# Schematic.net
KiCad netlist of a schematic drawn in EAGLE
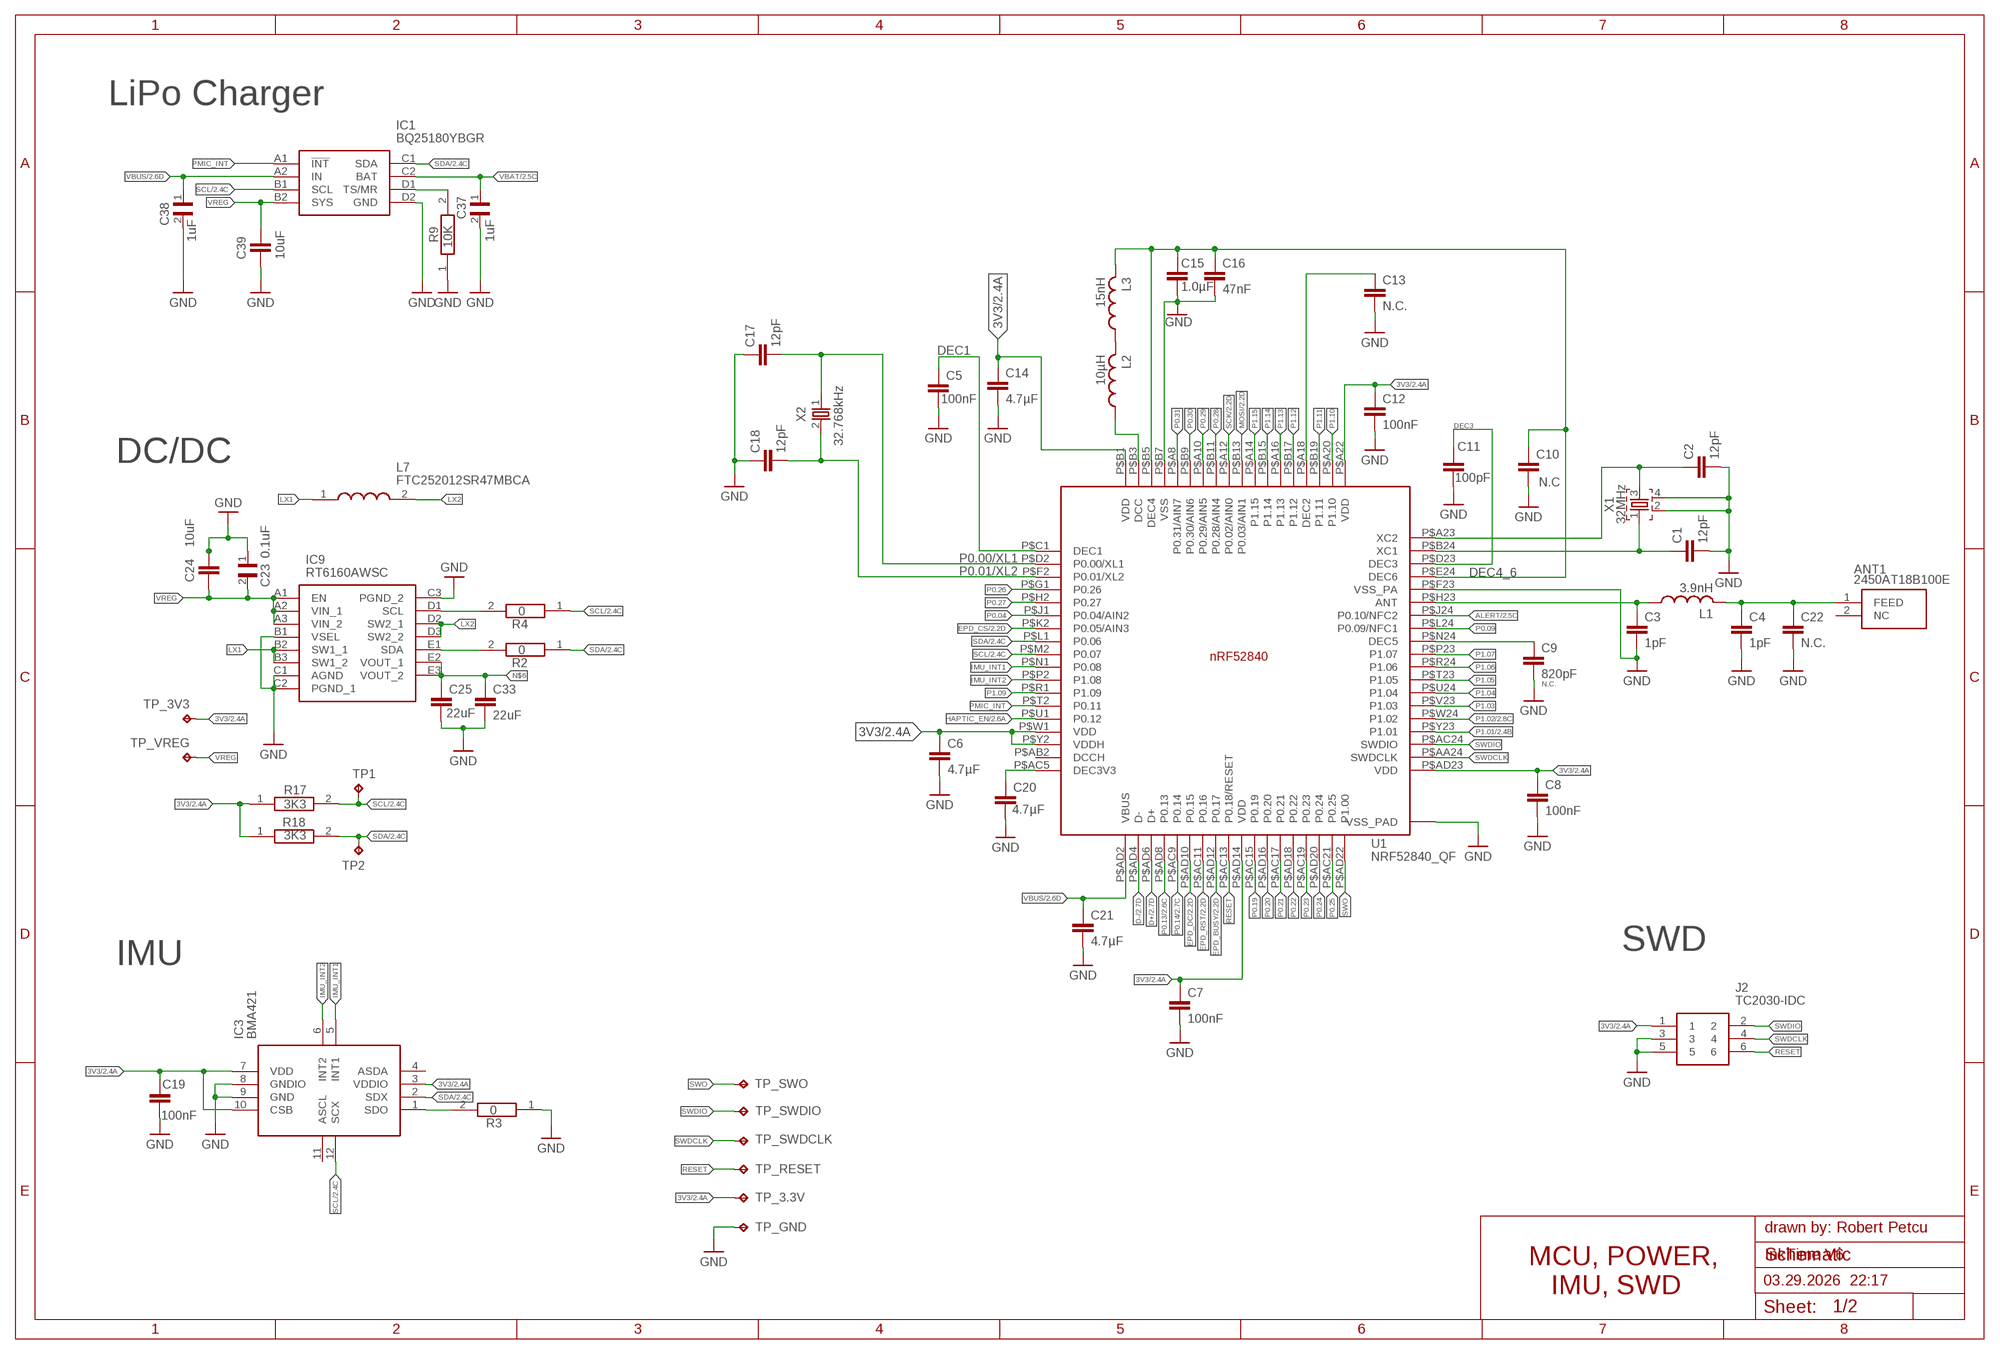
[diagram p0: schematic, sheet 1]
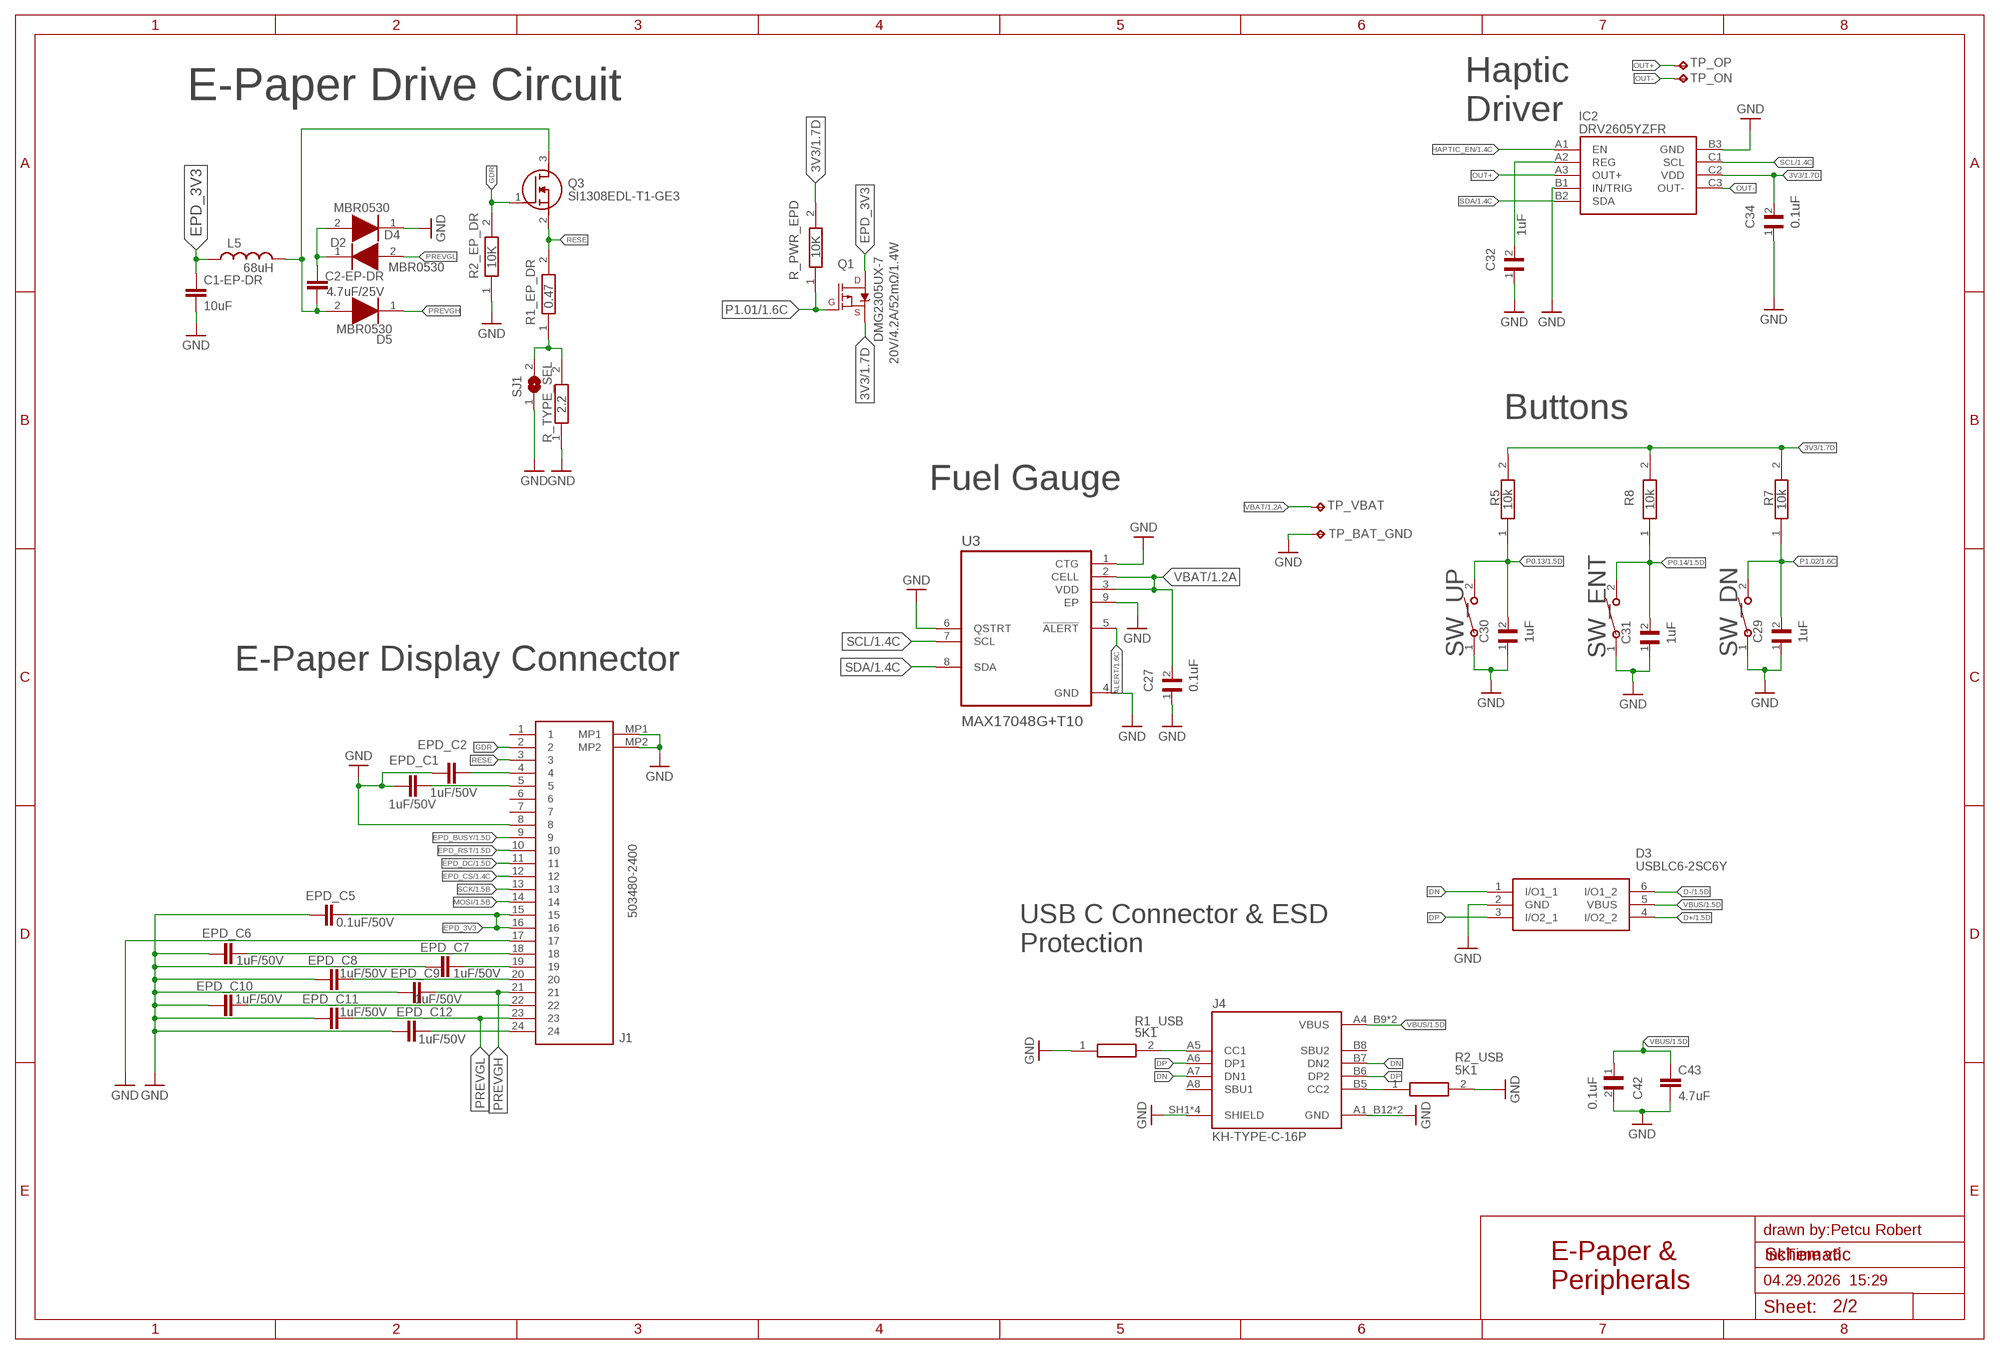
[diagram p1: schematic, sheet 2]

(export (version "E")
  (design (tool "Eeschema 10.0.6"))
  (components
    (comp (ref "ANT1")
      (value "2450AT18B100E")
      (footprint "eagle-import:2450AT18B100E_ANTC3216X140N")
      (fields (field (name "MOUSER_PART_NUMBER") "609-2450AT18B100E"))
      (libsource (lib "eagle-import") (part "2450AT18B100E_2450AT18B100E"))
    )
    (comp (ref "C1")
      (value "12pF")
      (footprint "eagle-import:NORDIC_NRF_3_RESC0201_L")
      (libsource (lib "eagle-import") (part "NORDIC_NRF_3_CAPACITOR_0201_L"))
    )
    (comp (ref "C2")
      (value "12pF")
      (footprint "eagle-import:NORDIC_NRF_3_RESC0201_L")
      (libsource (lib "eagle-import") (part "NORDIC_NRF_3_CAPACITOR_0201_L"))
    )
    (comp (ref "C3")
      (value "1pF")
      (footprint "eagle-import:NORDIC_NRF_3_RESC0201_L")
      (libsource (lib "eagle-import") (part "NORDIC_NRF_3_CAPACITOR_0201_L"))
    )
    (comp (ref "C4")
      (value "1pF")
      (footprint "eagle-import:NORDIC_NRF_3_RESC0201_L")
      (libsource (lib "eagle-import") (part "NORDIC_NRF_3_CAPACITOR_0201_L"))
    )
    (comp (ref "C5")
      (value "100nF")
      (footprint "eagle-import:NORDIC_NRF_3_RESC0201_L")
      (libsource (lib "eagle-import") (part "NORDIC_NRF_3_CAPACITOR_0201_L"))
    )
    (comp (ref "C6")
      (value "4.7µF")
      (footprint "eagle-import:PERFECT_0402_0402")
      (libsource (lib "eagle-import") (part "PERFECT_0402_CAP_0402"))
    )
    (comp (ref "C7")
      (value "100nF")
      (footprint "eagle-import:NORDIC_NRF_3_RESC0201_L")
      (libsource (lib "eagle-import") (part "NORDIC_NRF_3_CAPACITOR_0201_L"))
    )
    (comp (ref "C8")
      (value "100nF")
      (footprint "eagle-import:NORDIC_NRF_3_RESC0201_L")
      (libsource (lib "eagle-import") (part "NORDIC_NRF_3_CAPACITOR_0201_L"))
    )
    (comp (ref "C9")
      (value "820pF")
      (footprint "eagle-import:NORDIC_NRF_3_RESC0201_L")
      (libsource (lib "eagle-import") (part "NORDIC_NRF_3_CAPACITOR_0201_L"))
    )
    (comp (ref "C10")
      (value "N.C")
      (footprint "eagle-import:NORDIC_NRF_3_RESC0201_L")
      (libsource (lib "eagle-import") (part "NORDIC_NRF_3_CAPACITOR_0201_L"))
    )
    (comp (ref "C11")
      (value "100pF")
      (footprint "eagle-import:NORDIC_NRF_3_RESC0201_L")
      (libsource (lib "eagle-import") (part "NORDIC_NRF_3_CAPACITOR_0201_L"))
    )
    (comp (ref "C12")
      (value "100nF")
      (footprint "eagle-import:NORDIC_NRF_3_RESC0201_L")
      (libsource (lib "eagle-import") (part "NORDIC_NRF_3_CAPACITOR_0201_L"))
    )
    (comp (ref "C13")
      (value "N.C.")
      (footprint "eagle-import:NORDIC_NRF_3_RESC0201_L")
      (libsource (lib "eagle-import") (part "NORDIC_NRF_3_CAPACITOR_0201_L"))
    )
    (comp (ref "C14")
      (value "4.7µF")
      (footprint "eagle-import:PERFECT_0402_0402")
      (libsource (lib "eagle-import") (part "PERFECT_0402_CAP_0402"))
    )
    (comp (ref "C15")
      (value "1.0µF")
      (footprint "eagle-import:PERFECT_0402_0402")
      (libsource (lib "eagle-import") (part "PERFECT_0402_CAP_0402"))
    )
    (comp (ref "C16")
      (value "47nF")
      (footprint "eagle-import:NORDIC_NRF_3_RESC0201_L")
      (libsource (lib "eagle-import") (part "NORDIC_NRF_3_CAPACITOR_0201_L"))
    )
    (comp (ref "C17")
      (value "12pF")
      (footprint "eagle-import:NORDIC_NRF_3_RESC0201_L")
      (libsource (lib "eagle-import") (part "NORDIC_NRF_3_CAPACITOR_0201_L"))
    )
    (comp (ref "C18")
      (value "12pF")
      (footprint "eagle-import:NORDIC_NRF_3_RESC0201_L")
      (libsource (lib "eagle-import") (part "NORDIC_NRF_3_CAPACITOR_0201_L"))
    )
    (comp (ref "C19")
      (value "100nF")
      (footprint "eagle-import:NORDIC_NRF_3_RESC0201_L")
      (libsource (lib "eagle-import") (part "NORDIC_NRF_3_CAPACITOR_0201_L"))
    )
    (comp (ref "C20")
      (value "4.7µF")
      (footprint "eagle-import:PERFECT_0402_0402")
      (libsource (lib "eagle-import") (part "PERFECT_0402_CAP_0402"))
    )
    (comp (ref "C21")
      (value "4.7µF")
      (footprint "eagle-import:PERFECT_0402_0402")
      (libsource (lib "eagle-import") (part "PERFECT_0402_CAP_0402"))
    )
    (comp (ref "C22")
      (value "N.C.")
      (footprint "eagle-import:NORDIC_NRF_3_RESC0201_L")
      (libsource (lib "eagle-import") (part "NORDIC_NRF_3_CAPACITOR_0201_L"))
    )
    (comp (ref "C23")
      (value "0.1uF")
      (footprint "eagle-import:GRM011R60J152KE01L_1_0201")
      (libsource (lib "eagle-import") (part "GRM011R60J152KE01L_1_GRM011R60J152KE01L"))
    )
    (comp (ref "C24")
      (value "10uF")
      (footprint "eagle-import:PERFECT_0402_0402")
      (libsource (lib "eagle-import") (part "PERFECT_0402_CAP_0402"))
    )
    (comp (ref "C25")
      (value "22uF")
      (footprint "eagle-import:PERFECT_0402_0402")
      (libsource (lib "eagle-import") (part "PERFECT_0402_CAP_0402"))
    )
    (comp (ref "C33")
      (value "22uF")
      (footprint "eagle-import:PERFECT_0402_0402")
      (libsource (lib "eagle-import") (part "PERFECT_0402_CAP_0402"))
    )
    (comp (ref "C37")
      (value "1uF")
      (footprint "eagle-import:GRM011R60J152KE01L_1_0201")
      (libsource (lib "eagle-import") (part "GRM011R60J152KE01L_1_GRM011R60J152KE01L"))
    )
    (comp (ref "C38")
      (value "1uF")
      (footprint "eagle-import:GRM011R60J152KE01L_1_0201")
      (libsource (lib "eagle-import") (part "GRM011R60J152KE01L_1_GRM011R60J152KE01L"))
    )
    (comp (ref "C39")
      (value "10uF")
      (footprint "eagle-import:PERFECT_0402_0402")
      (libsource (lib "eagle-import") (part "PERFECT_0402_CAP_0402"))
    )
    (comp (ref "IC1")
      (value "BQ25180YBGR")
      (footprint "eagle-import:BQ25180YBGR_BGA8C40P2X4_100X155X50")
      (fields (field (name "MOUSER_PART_NUMBER") "595-BQ25180YBGR"))
      (libsource (lib "eagle-import") (part "BQ25180YBGR_BQ25180YBGR"))
    )
    (comp (ref "IC3")
      (value "BMA421")
      (footprint "eagle-import:BMA423_BMA423")
      (fields (field (name "ARROW_PART_NUMBER") "BMA423") (field (name "MOUSER_PART_NUMBER") "262-BMA423"))
      (libsource (lib "eagle-import") (part "BMA423_BMA423"))
    )
    (comp (ref "IC9")
      (value "RT6160AWSC")
      (footprint "eagle-import:RT6160AWSC_BGA15C40P3X5_140X230X60")
      (fields (field (name "MOUSER_PART_NUMBER") "835-RT6160AWSC"))
      (libsource (lib "eagle-import") (part "RT6160AWSC_RT6160AWSC"))
    )
    (comp (ref "J2")
      (value "TC2030-IDC")
      (footprint "eagle-import:TC2030-IDC_TC2030IDC")
      (libsource (lib "eagle-import") (part "TC2030-IDC_TC2030-IDC"))
    )
    (comp (ref "L1")
      (value "3.9nH")
      (footprint "eagle-import:NORDIC_NRF_2_RESC0402_L")
      (libsource (lib "eagle-import") (part "NORDIC_NRF_2_INDUCTOR_0402_L"))
    )
    (comp (ref "L2")
      (value "10µH")
      (footprint "eagle-import:NORDIC_NRF_2_RESC0402_L")
      (libsource (lib "eagle-import") (part "NORDIC_NRF_2_INDUCTOR_0402_L"))
    )
    (comp (ref "L3")
      (value "15nH")
      (footprint "eagle-import:NORDIC_NRF_2_RESC0402_L")
      (libsource (lib "eagle-import") (part "NORDIC_NRF_2_INDUCTOR_0402_L"))
    )
    (comp (ref "L7")
      (value "FTC252012SR47MBCA")
      (footprint "eagle-import:MLP2016SR47MT0S1_INDC2016X100N")
      (libsource (lib "eagle-import") (part "MLP2016SR47MT0S1_FTC252012SR47MBCA"))
    )
    (comp (ref "R2")
      (value "0")
      (footprint "eagle-import:CPF0201D7K68C1_0201")
      (libsource (lib "eagle-import") (part "CPF0201D7K68C1_CPF0201D7K68C1"))
    )
    (comp (ref "R3")
      (value "0")
      (footprint "eagle-import:CPF0201D7K68C1_0201")
      (libsource (lib "eagle-import") (part "CPF0201D7K68C1_CPF0201D7K68C1"))
    )
    (comp (ref "R4")
      (value "0")
      (footprint "eagle-import:CPF0201D7K68C1_0201")
      (libsource (lib "eagle-import") (part "CPF0201D7K68C1_CPF0201D7K68C1"))
    )
    (comp (ref "R9")
      (value "10K")
      (footprint "eagle-import:CPF0201D7K68C1_0201")
      (libsource (lib "eagle-import") (part "CPF0201D7K68C1_CPF0201D7K68C1"))
    )
    (comp (ref "R17")
      (value "3K3")
      (footprint "eagle-import:CPF0201D7K68C1_0201")
      (libsource (lib "eagle-import") (part "CPF0201D7K68C1_CPF0201D7K68C1"))
    )
    (comp (ref "R18")
      (value "3K3")
      (footprint "eagle-import:CPF0201D7K68C1_0201")
      (libsource (lib "eagle-import") (part "CPF0201D7K68C1_CPF0201D7K68C1"))
    )
    (comp (ref "TP1")
      (value "HECTOR_WATCH_1_TPTP20R")
      (footprint "eagle-import:HECTOR_WATCH_1_TP20R")
      (libsource (lib "eagle-import") (part "HECTOR_WATCH_1_TPTP20R"))
    )
    (comp (ref "TP2")
      (value "HECTOR_WATCH_1_TPTP20R")
      (footprint "eagle-import:HECTOR_WATCH_1_TP20R")
      (libsource (lib "eagle-import") (part "HECTOR_WATCH_1_TPTP20R"))
    )
    (comp (ref "TP_3.3V")
      (value "HECTOR_WATCH_1_TPTP20R")
      (footprint "eagle-import:HECTOR_WATCH_1_TP20R")
      (libsource (lib "eagle-import") (part "HECTOR_WATCH_1_TPTP20R"))
    )
    (comp (ref "TP_3V3")
      (value "HECTOR_WATCH_1_TPTP20R")
      (footprint "eagle-import:HECTOR_WATCH_1_TP20R")
      (libsource (lib "eagle-import") (part "HECTOR_WATCH_1_TPTP20R"))
    )
    (comp (ref "TP_GND")
      (value "HECTOR_WATCH_1_TPTP20R")
      (footprint "eagle-import:HECTOR_WATCH_1_TP20R")
      (libsource (lib "eagle-import") (part "HECTOR_WATCH_1_TPTP20R"))
    )
    (comp (ref "TP_RESET")
      (value "HECTOR_WATCH_1_TPTP20R")
      (footprint "eagle-import:HECTOR_WATCH_1_TP20R")
      (libsource (lib "eagle-import") (part "HECTOR_WATCH_1_TPTP20R"))
    )
    (comp (ref "TP_SWDCLK")
      (value "HECTOR_WATCH_1_TPTP20R")
      (footprint "eagle-import:HECTOR_WATCH_1_TP20R")
      (libsource (lib "eagle-import") (part "HECTOR_WATCH_1_TPTP20R"))
    )
    (comp (ref "TP_SWDIO")
      (value "HECTOR_WATCH_1_TPTP20R")
      (footprint "eagle-import:HECTOR_WATCH_1_TP20R")
      (libsource (lib "eagle-import") (part "HECTOR_WATCH_1_TPTP20R"))
    )
    (comp (ref "TP_SWO")
      (value "HECTOR_WATCH_1_TPTP20R")
      (footprint "eagle-import:HECTOR_WATCH_1_TP20R")
      (libsource (lib "eagle-import") (part "HECTOR_WATCH_1_TPTP20R"))
    )
    (comp (ref "TP_VREG")
      (value "HECTOR_WATCH_1_TPTP20R")
      (footprint "eagle-import:HECTOR_WATCH_1_TP20R")
      (libsource (lib "eagle-import") (part "HECTOR_WATCH_1_TPTP20R"))
    )
    (comp (ref "U1")
      (value "NRF52840_QF")
      (footprint "eagle-import:NORDIC_NRF_4_AQFN50P700X700X85_HS-74N")
      (libsource (lib "eagle-import") (part "NORDIC_NRF_4_NRF52840_QF"))
    )
    (comp (ref "X1")
      (value "32MHz")
      (footprint "eagle-import:NORDIC_NRF_BT-XTAL_2016_N")
      (libsource (lib "eagle-import") (part "NORDIC_NRF_XTAL_32MHZ"))
    )
    (comp (ref "X2")
      (value "32.768kHz")
      (footprint "eagle-import:NORDIC_NRF_1_XTAL_3215_N")
      (libsource (lib "eagle-import") (part "NORDIC_NRF_1_XTAL_32KHZ"))
    )
    (comp (ref "C1-EP-DR")
      (value "10uF")
      (footprint "eagle-import:PERFECT_0402_0402")
      (libsource (lib "eagle-import") (part "PERFECT_0402_CAP_0402"))
    )
    (comp (ref "C2-EP-DR")
      (value "4.7uF/25V")
      (footprint "eagle-import:PERFECT_0402_0402")
      (libsource (lib "eagle-import") (part "PERFECT_0402_CAP_0402"))
    )
    (comp (ref "C27")
      (value "0.1uF")
      (footprint "eagle-import:GRM011R60J152KE01L_1_0201")
      (libsource (lib "eagle-import") (part "GRM011R60J152KE01L_1_GRM011R60J152KE01L"))
    )
    (comp (ref "C29")
      (value "1uF")
      (footprint "eagle-import:GRM011R60J152KE01L_1_0201")
      (libsource (lib "eagle-import") (part "GRM011R60J152KE01L_1_GRM011R60J152KE01L"))
    )
    (comp (ref "C30")
      (value "1uF")
      (footprint "eagle-import:GRM011R60J152KE01L_1_0201")
      (libsource (lib "eagle-import") (part "GRM011R60J152KE01L_1_GRM011R60J152KE01L"))
    )
    (comp (ref "C31")
      (value "1uF")
      (footprint "eagle-import:GRM011R60J152KE01L_1_0201")
      (libsource (lib "eagle-import") (part "GRM011R60J152KE01L_1_GRM011R60J152KE01L"))
    )
    (comp (ref "C32")
      (value "1uF")
      (footprint "eagle-import:GRM011R60J152KE01L_1_0201")
      (libsource (lib "eagle-import") (part "GRM011R60J152KE01L_1_GRM011R60J152KE01L"))
    )
    (comp (ref "C34")
      (value "0.1uF")
      (footprint "eagle-import:GRM011R60J152KE01L_1_0201")
      (libsource (lib "eagle-import") (part "GRM011R60J152KE01L_1_GRM011R60J152KE01L"))
    )
    (comp (ref "C42")
      (value "0.1uF")
      (footprint "eagle-import:GRM011R60J152KE01L_1_0201")
      (libsource (lib "eagle-import") (part "GRM011R60J152KE01L_1_GRM011R60J152KE01L"))
    )
    (comp (ref "C43")
      (value "4.7uF")
      (footprint "eagle-import:PERFECT_0402_0402")
      (libsource (lib "eagle-import") (part "PERFECT_0402_CAP_0402"))
    )
    (comp (ref "D2")
      (value "MBR0530")
      (footprint "eagle-import:ESP32_C6_LIBRARY_5_SOD3716X135N")
      (fields (field (name "MF") "ON Semiconductor"))
      (libsource (lib "eagle-import") (part "ESP32_C6_LIBRARY_5_MBR0530"))
    )
    (comp (ref "D3")
      (value "USBLC6-2SC6Y")
      (footprint "eagle-import:ESP32_C6_LIBRARY_3_SOT95P280X145-6N")
      (fields (field (name "MF") "STMicroelectronics"))
      (libsource (lib "eagle-import") (part "ESP32_C6_LIBRARY_3_USBLC6-2SC6Y"))
    )
    (comp (ref "D4")
      (value "MBR0530")
      (footprint "eagle-import:ESP32_C6_LIBRARY_5_SOD3716X135N")
      (fields (field (name "MF") "ON Semiconductor"))
      (libsource (lib "eagle-import") (part "ESP32_C6_LIBRARY_5_MBR0530"))
    )
    (comp (ref "D5")
      (value "MBR0530")
      (footprint "eagle-import:ESP32_C6_LIBRARY_5_SOD3716X135N")
      (fields (field (name "MF") "ON Semiconductor"))
      (libsource (lib "eagle-import") (part "ESP32_C6_LIBRARY_5_MBR0530"))
    )
    (comp (ref "DMG2305UX-7")
      (value "20V/4.2A/52mΩ/1.4W")
      (footprint "eagle-import:ESP32_C6_LIBRARY_4_ESP32_C6_LIBRARY_4_ESP32_C6_LIBRARY_4_ESP32_C6_LIBRARY_4_ESP32_WROVER_SPARKFUN-DISCRETESEMI_SOT23-3")
      (libsource (lib "eagle-import") (part "ESP32_C6_LIBRARY_4_ESP32_WROVER_SPARKFUN-DISCRETESEMI_MOSFET_PCH-DMG2305UX-7"))
    )
    (comp (ref "EPD_C1")
      (value "1uF/50V")
      (footprint "eagle-import:PERFECT_0402_0402")
      (libsource (lib "eagle-import") (part "PERFECT_0402_CAP_0402"))
    )
    (comp (ref "EPD_C2")
      (value "1uF/50V")
      (footprint "eagle-import:PERFECT_0402_0402")
      (libsource (lib "eagle-import") (part "PERFECT_0402_CAP_0402"))
    )
    (comp (ref "EPD_C5")
      (value "0.1uF/50V")
      (footprint "eagle-import:NORDIC_NRF_3_RESC0201_L")
      (libsource (lib "eagle-import") (part "NORDIC_NRF_3_CAPACITOR_0201_L"))
    )
    (comp (ref "EPD_C6")
      (value "1uF/50V")
      (footprint "eagle-import:PERFECT_0402_0402")
      (libsource (lib "eagle-import") (part "PERFECT_0402_CAP_0402"))
    )
    (comp (ref "EPD_C7")
      (value "1uF/50V")
      (footprint "eagle-import:PERFECT_0402_0402")
      (libsource (lib "eagle-import") (part "PERFECT_0402_CAP_0402"))
    )
    (comp (ref "EPD_C8")
      (value "1uF/50V")
      (footprint "eagle-import:PERFECT_0402_0402")
      (libsource (lib "eagle-import") (part "PERFECT_0402_CAP_0402"))
    )
    (comp (ref "EPD_C9")
      (value "1uF/50V")
      (footprint "eagle-import:PERFECT_0402_0402")
      (libsource (lib "eagle-import") (part "PERFECT_0402_CAP_0402"))
    )
    (comp (ref "EPD_C10")
      (value "1uF/50V")
      (footprint "eagle-import:PERFECT_0402_0402")
      (libsource (lib "eagle-import") (part "PERFECT_0402_CAP_0402"))
    )
    (comp (ref "EPD_C11")
      (value "1uF/50V")
      (footprint "eagle-import:PERFECT_0402_0402")
      (libsource (lib "eagle-import") (part "PERFECT_0402_CAP_0402"))
    )
    (comp (ref "EPD_C12")
      (value "1uF/50V")
      (footprint "eagle-import:PERFECT_0402_0402")
      (libsource (lib "eagle-import") (part "PERFECT_0402_CAP_0402"))
    )
    (comp (ref "IC2")
      (value "DRV2605YZFR")
      (footprint "eagle-import:DRV2605YZFR_BGA9C50P3X3_144X144X62")
      (libsource (lib "eagle-import") (part "DRV2605YZFR_DRV2605YZFR"))
    )
    (comp (ref "J1")
      (value "503480-2400")
      (footprint "eagle-import:503480-2400_5034802400")
      (fields (field (name "MOUSER_PART_NUMBER") "538-503480-2400"))
      (libsource (lib "eagle-import") (part "503480-2400_503480-2400"))
    )
    (comp (ref "J4")
      (value "KH-TYPE-C-16P")
      (footprint "eagle-import:KH-TYPE-C-16P_KINGHELM_KH-TYPE-C-16P")
      (fields (field (name "MF") "kinghelm"))
      (libsource (lib "eagle-import") (part "KH-TYPE-C-16P_KH-TYPE-C-16P"))
    )
    (comp (ref "L5")
      (value "68uH")
      (footprint "eagle-import:NORDIC_NRF_2_RESC0402_L")
      (libsource (lib "eagle-import") (part "NORDIC_NRF_2_INDUCTOR_0402_L"))
    )
    (comp (ref "Q3")
      (value "SI1308EDL-T1-GE3")
      (footprint "eagle-import:ESP32_C6_LIBRARY_6_SOT65P210X110-3N")
      (fields (field (name "MF") "Vishay Siliconix"))
      (libsource (lib "eagle-import") (part "ESP32_C6_LIBRARY_6_SI1308EDL-T1-GE3"))
    )
    (comp (ref "R1_EP_DR")
      (value "0.47")
      (footprint "eagle-import:CPF0201D7K68C1_0201")
      (libsource (lib "eagle-import") (part "CPF0201D7K68C1_CPF0201D7K68C1"))
    )
    (comp (ref "R1_USB")
      (value "5K1")
      (footprint "eagle-import:CPF0201D7K68C1_0201")
      (libsource (lib "eagle-import") (part "CPF0201D7K68C1_CPF0201D7K68C1"))
    )
    (comp (ref "R2_EP_DR")
      (value "10K")
      (footprint "eagle-import:CPF0201D7K68C1_0201")
      (libsource (lib "eagle-import") (part "CPF0201D7K68C1_CPF0201D7K68C1"))
    )
    (comp (ref "R2_USB")
      (value "5K1")
      (footprint "eagle-import:CPF0201D7K68C1_0201")
      (libsource (lib "eagle-import") (part "CPF0201D7K68C1_CPF0201D7K68C1"))
    )
    (comp (ref "R5")
      (value "10k")
      (footprint "eagle-import:CPF0201D7K68C1_0201")
      (libsource (lib "eagle-import") (part "CPF0201D7K68C1_CPF0201D7K68C1"))
    )
    (comp (ref "R7")
      (value "10k")
      (footprint "eagle-import:CPF0201D7K68C1_0201")
      (libsource (lib "eagle-import") (part "CPF0201D7K68C1_CPF0201D7K68C1"))
    )
    (comp (ref "R8")
      (value "10k")
      (footprint "eagle-import:CPF0201D7K68C1_0201")
      (libsource (lib "eagle-import") (part "CPF0201D7K68C1_CPF0201D7K68C1"))
    )
    (comp (ref "R_PWR_EPD")
      (value "10K")
      (footprint "eagle-import:CPF0201D7K68C1_0201")
      (libsource (lib "eagle-import") (part "CPF0201D7K68C1_CPF0201D7K68C1"))
    )
    (comp (ref "R_TYPE_SEL")
      (value "2.2")
      (footprint "eagle-import:CPF0201D7K68C1_0201")
      (libsource (lib "eagle-import") (part "CPF0201D7K68C1_CPF0201D7K68C1"))
    )
    (comp (ref "SJ1")
      (value "ESP32_C6_LIBRARY_7_JUMPER_SJ")
      (footprint "eagle-import:ESP32_C6_LIBRARY_7_JUMPER_SJ")
      (libsource (lib "eagle-import") (part "ESP32_C6_LIBRARY_7_JUMPER_SJ"))
    )
    (comp (ref "SW_DN")
      (value "2025-10-22_07-23-44_LIBRARY_EVP-AKE31ASW_EVP-AKE31A_PAN")
      (footprint "eagle-import:2025-10-22_07-23-44_LIBRARY_SW_EVP-AKE31A_PAN")
      (fields
        (field (name "MANUFACTURER_PART_NUMBER") "EVP-AKE31A")
        (field (name "COPYRIGHT") "Copyright (C) 2025 Ultra Librarian. All rights reserved.")
      )
      (libsource (lib "eagle-import") (part "2025-10-22_07-23-44_LIBRARY_EVP-AKE31ASW_EVP-AKE31A_PAN"))
    )
    (comp (ref "SW_ENT")
      (value "2025-10-22_07-23-44_LIBRARY_EVP-AKE31ASW_EVP-AKE31A_PAN")
      (footprint "eagle-import:2025-10-22_07-23-44_LIBRARY_SW_EVP-AKE31A_PAN")
      (fields
        (field (name "MANUFACTURER_PART_NUMBER") "EVP-AKE31A")
        (field (name "COPYRIGHT") "Copyright (C) 2025 Ultra Librarian. All rights reserved.")
      )
      (libsource (lib "eagle-import") (part "2025-10-22_07-23-44_LIBRARY_EVP-AKE31ASW_EVP-AKE31A_PAN"))
    )
    (comp (ref "SW_UP")
      (value "2025-10-22_07-23-44_LIBRARY_EVP-AKE31ASW_EVP-AKE31A_PAN")
      (footprint "eagle-import:2025-10-22_07-23-44_LIBRARY_SW_EVP-AKE31A_PAN")
      (fields
        (field (name "MANUFACTURER_PART_NUMBER") "EVP-AKE31A")
        (field (name "COPYRIGHT") "Copyright (C) 2025 Ultra Librarian. All rights reserved.")
      )
      (libsource (lib "eagle-import") (part "2025-10-22_07-23-44_LIBRARY_EVP-AKE31ASW_EVP-AKE31A_PAN"))
    )
    (comp (ref "TP_BAT_GND")
      (value "HECTOR_WATCH_1_TPTP20R")
      (footprint "eagle-import:HECTOR_WATCH_1_TP20R")
      (libsource (lib "eagle-import") (part "HECTOR_WATCH_1_TPTP20R"))
    )
    (comp (ref "TP_ON")
      (value "HECTOR_WATCH_1_TPTP20R")
      (footprint "eagle-import:HECTOR_WATCH_1_TP20R")
      (libsource (lib "eagle-import") (part "HECTOR_WATCH_1_TPTP20R"))
    )
    (comp (ref "TP_OP")
      (value "HECTOR_WATCH_1_TPTP20R")
      (footprint "eagle-import:HECTOR_WATCH_1_TP20R")
      (libsource (lib "eagle-import") (part "HECTOR_WATCH_1_TPTP20R"))
    )
    (comp (ref "TP_VBAT")
      (value "HECTOR_WATCH_1_TPTP20R")
      (footprint "eagle-import:HECTOR_WATCH_1_TP20R")
      (libsource (lib "eagle-import") (part "HECTOR_WATCH_1_TPTP20R"))
    )
    (comp (ref "U3")
      (value "MAX17048G+T10")
      (footprint "eagle-import:ESP32_C6_LIBRARY_SON50P200X200X80-9N")
      (fields (field (name "MF") "Analog Devices"))
      (libsource (lib "eagle-import") (part "ESP32_C6_LIBRARY_MAX17048G+T10"))
    )
  )
  (nets
    (net (code "1") (name "3V3{slash}1.7D") (class "Default")
      (node (ref "C34") (pin "2") (pinfunction "2_2") (pintype "passive"))
      (node (ref "DMG2305UX-7") (pin "2") (pinfunction "S_2") (pintype "bidirectional"))
      (node (ref "IC2") (pin "C2") (pinfunction "VDD_C2") (pintype "bidirectional"))
      (node (ref "R5") (pin "2") (pinfunction "2_2") (pintype "bidirectional"))
      (node (ref "R7") (pin "2") (pinfunction "2_2") (pintype "bidirectional"))
      (node (ref "R8") (pin "2") (pinfunction "2_2") (pintype "bidirectional"))
      (node (ref "R_PWR_EPD") (pin "2") (pinfunction "2_2") (pintype "bidirectional"))
    )
    (net (code "2") (name "3V3{slash}2.4A") (class "Default")
      (node (ref "C12") (pin "1") (pinfunction "1_1") (pintype "passive"))
      (node (ref "C14") (pin "1") (pinfunction "1_1") (pintype "passive"))
      (node (ref "C19") (pin "1") (pinfunction "1_1") (pintype "passive"))
      (node (ref "C6") (pin "1") (pinfunction "1_1") (pintype "passive"))
      (node (ref "C7") (pin "1") (pinfunction "1_1") (pintype "passive"))
      (node (ref "C8") (pin "1") (pinfunction "1_1") (pintype "passive"))
      (node (ref "IC3") (pin "10") (pinfunction "CSB_10") (pintype "bidirectional"))
      (node (ref "IC3") (pin "3") (pinfunction "VDDIO_3") (pintype "bidirectional"))
      (node (ref "IC3") (pin "7") (pinfunction "VDD_7") (pintype "bidirectional"))
      (node (ref "J2") (pin "1") (pinfunction "1_1") (pintype "bidirectional"))
      (node (ref "R17") (pin "1") (pinfunction "1_1") (pintype "bidirectional"))
      (node (ref "R18") (pin "1") (pinfunction "1_1") (pintype "bidirectional"))
      (node (ref "TP_3.3V") (pin "TP") (pinfunction "TP_TP") (pintype "input"))
      (node (ref "TP_3V3") (pin "TP") (pinfunction "TP_TP") (pintype "input"))
      (node (ref "U1") (pin "P$A22") (pinfunction "VDD_P$A22") (pintype "power_in"))
      (node (ref "U1") (pin "P$AD14") (pinfunction "VDD_P$AD14") (pintype "power_in"))
      (node (ref "U1") (pin "P$AD23") (pinfunction "VDD_P$AD23") (pintype "power_in"))
      (node (ref "U1") (pin "P$B1") (pinfunction "VDD_P$B1") (pintype "power_in"))
      (node (ref "U1") (pin "P$W1") (pinfunction "VDD_P$W1") (pintype "power_in"))
      (node (ref "U1") (pin "P$Y2") (pinfunction "VDDH_P$Y2") (pintype "power_in"))
    )
    (net (code "3") (name "ALERT{slash}1.6C") (class "Default")
      (node (ref "U3") (pin "5") (pinfunction "~{ALERT}_5") (pintype "output"))
    )
    (net (code "4") (name "ALERT{slash}2.5C") (class "Default")
      (node (ref "U1") (pin "P$J24") (pinfunction "P0.10/NFC2_P$J24") (pintype "bidirectional"))
    )
    (net (code "5") (name "D+{slash}1.5D") (class "Default")
      (node (ref "D3") (pin "4") (pinfunction "I/O2_2_4") (pintype "bidirectional"))
    )
    (net (code "6") (name "D+{slash}2.7D") (class "Default")
      (node (ref "U1") (pin "P$AD6") (pinfunction "D+_P$AD6") (pintype "bidirectional"))
    )
    (net (code "7") (name "D-{slash}1.5D") (class "Default")
      (node (ref "D3") (pin "6") (pinfunction "I/O1_2_6") (pintype "bidirectional"))
    )
    (net (code "8") (name "D-{slash}2.7D") (class "Default")
      (node (ref "U1") (pin "P$AD4") (pinfunction "D-_P$AD4") (pintype "bidirectional"))
    )
    (net (code "9") (name "DEC1") (class "Default")
      (node (ref "C5") (pin "1") (pinfunction "1_1") (pintype "passive"))
      (node (ref "U1") (pin "P$C1") (pinfunction "DEC1_P$C1") (pintype "power_in"))
    )
    (net (code "10") (name "DEC3") (class "Default")
      (node (ref "C11") (pin "1") (pinfunction "1_1") (pintype "passive"))
      (node (ref "U1") (pin "P$D23") (pinfunction "DEC3_P$D23") (pintype "bidirectional"))
    )
    (net (code "11") (name "DEC4_6") (class "Default")
      (node (ref "C10") (pin "1") (pinfunction "1_1") (pintype "passive"))
      (node (ref "C15") (pin "1") (pinfunction "1_1") (pintype "passive"))
      (node (ref "C16") (pin "1") (pinfunction "1_1") (pintype "passive"))
      (node (ref "L3") (pin "2") (pinfunction "2_2") (pintype "passive"))
      (node (ref "U1") (pin "P$B5") (pinfunction "DEC4_P$B5") (pintype "power_in"))
      (node (ref "U1") (pin "P$E24") (pinfunction "DEC6_P$E24") (pintype "bidirectional"))
    )
    (net (code "12") (name "DN") (class "Default")
      (node (ref "D3") (pin "1") (pinfunction "I/O1_1_1") (pintype "bidirectional"))
      (node (ref "J4") (pin "A7") (pinfunction "DN1_A7") (pintype "bidirectional"))
      (node (ref "J4") (pin "B7") (pinfunction "DN2_B7") (pintype "bidirectional"))
    )
    (net (code "13") (name "DP") (class "Default")
      (node (ref "D3") (pin "3") (pinfunction "I/O2_1_3") (pintype "bidirectional"))
      (node (ref "J4") (pin "A6") (pinfunction "DP1_A6") (pintype "bidirectional"))
      (node (ref "J4") (pin "B6") (pinfunction "DP2_B6") (pintype "bidirectional"))
    )
    (net (code "14") (name "EPD_3V3") (class "Default")
      (node (ref "C1-EP-DR") (pin "1") (pinfunction "1_1") (pintype "passive"))
      (node (ref "DMG2305UX-7") (pin "3") (pinfunction "D_3") (pintype "bidirectional"))
      (node (ref "EPD_C5") (pin "2") (pinfunction "2_2") (pintype "passive"))
      (node (ref "J1") (pin "15") (pinfunction "15_15") (pintype "bidirectional"))
      (node (ref "J1") (pin "16") (pinfunction "16_16") (pintype "bidirectional"))
      (node (ref "L5") (pin "1") (pinfunction "1_1") (pintype "passive"))
    )
    (net (code "15") (name "EPD_BUSY{slash}1.5D") (class "Default")
      (node (ref "J1") (pin "9") (pinfunction "9_9") (pintype "bidirectional"))
    )
    (net (code "16") (name "EPD_BUSY{slash}2.2D") (class "Default")
      (node (ref "U1") (pin "P$AD12") (pinfunction "P0.17_P$AD12") (pintype "bidirectional"))
    )
    (net (code "17") (name "EPD_CS{slash}1.4C") (class "Default")
      (node (ref "J1") (pin "12") (pinfunction "12_12") (pintype "bidirectional"))
    )
    (net (code "18") (name "EPD_CS{slash}2.2D") (class "Default")
      (node (ref "U1") (pin "P$K2") (pinfunction "P0.05/AIN3_P$K2") (pintype "bidirectional"))
    )
    (net (code "19") (name "EPD_DC{slash}1.5D") (class "Default")
      (node (ref "J1") (pin "11") (pinfunction "11_11") (pintype "bidirectional"))
    )
    (net (code "20") (name "EPD_DC{slash}2.2D") (class "Default")
      (node (ref "U1") (pin "P$AD10") (pinfunction "P0.15_P$AD10") (pintype "bidirectional"))
    )
    (net (code "21") (name "EPD_RST{slash}1.5D") (class "Default")
      (node (ref "J1") (pin "10") (pinfunction "10_10") (pintype "bidirectional"))
    )
    (net (code "22") (name "EPD_RST{slash}2.2D") (class "Default")
      (node (ref "U1") (pin "P$AC11") (pinfunction "P0.16_P$AC11") (pintype "bidirectional"))
    )
    (net (code "23") (name "GDR") (class "Default")
      (node (ref "J1") (pin "2") (pinfunction "2_2") (pintype "bidirectional"))
      (node (ref "Q3") (pin "1") (pinfunction "G_1") (pintype "bidirectional"))
      (node (ref "R2_EP_DR") (pin "2") (pinfunction "2_2") (pintype "bidirectional"))
    )
    (net (code "24") (name "GND") (class "Default")
      (node (ref "C1") (pin "2") (pinfunction "2_2") (pintype "passive"))
      (node (ref "C1-EP-DR") (pin "2") (pinfunction "2_2") (pintype "passive"))
      (node (ref "C10") (pin "2") (pinfunction "2_2") (pintype "passive"))
      (node (ref "C11") (pin "2") (pinfunction "2_2") (pintype "passive"))
      (node (ref "C12") (pin "2") (pinfunction "2_2") (pintype "passive"))
      (node (ref "C13") (pin "2") (pinfunction "2_2") (pintype "passive"))
      (node (ref "C14") (pin "2") (pinfunction "2_2") (pintype "passive"))
      (node (ref "C15") (pin "2") (pinfunction "2_2") (pintype "passive"))
      (node (ref "C16") (pin "2") (pinfunction "2_2") (pintype "passive"))
      (node (ref "C17") (pin "1") (pinfunction "1_1") (pintype "passive"))
      (node (ref "C18") (pin "1") (pinfunction "1_1") (pintype "passive"))
      (node (ref "C19") (pin "2") (pinfunction "2_2") (pintype "passive"))
      (node (ref "C2") (pin "2") (pinfunction "2_2") (pintype "passive"))
      (node (ref "C20") (pin "2") (pinfunction "2_2") (pintype "passive"))
      (node (ref "C21") (pin "2") (pinfunction "2_2") (pintype "passive"))
      (node (ref "C22") (pin "2") (pinfunction "2_2") (pintype "passive"))
      (node (ref "C23") (pin "1") (pinfunction "1_1") (pintype "passive"))
      (node (ref "C24") (pin "1") (pinfunction "1_1") (pintype "passive"))
      (node (ref "C25") (pin "2") (pinfunction "2_2") (pintype "passive"))
      (node (ref "C27") (pin "1") (pinfunction "1_1") (pintype "passive"))
      (node (ref "C29") (pin "1") (pinfunction "1_1") (pintype "passive"))
      (node (ref "C3") (pin "2") (pinfunction "2_2") (pintype "passive"))
      (node (ref "C30") (pin "1") (pinfunction "1_1") (pintype "passive"))
      (node (ref "C31") (pin "1") (pinfunction "1_1") (pintype "passive"))
      (node (ref "C32") (pin "1") (pinfunction "1_1") (pintype "passive"))
      (node (ref "C33") (pin "2") (pinfunction "2_2") (pintype "passive"))
      (node (ref "C34") (pin "1") (pinfunction "1_1") (pintype "passive"))
      (node (ref "C37") (pin "2") (pinfunction "2_2") (pintype "passive"))
      (node (ref "C38") (pin "2") (pinfunction "2_2") (pintype "passive"))
      (node (ref "C39") (pin "2") (pinfunction "2_2") (pintype "passive"))
      (node (ref "C4") (pin "2") (pinfunction "2_2") (pintype "passive"))
      (node (ref "C42") (pin "2") (pinfunction "2_2") (pintype "passive"))
      (node (ref "C43") (pin "2") (pinfunction "2_2") (pintype "passive"))
      (node (ref "C5") (pin "2") (pinfunction "2_2") (pintype "passive"))
      (node (ref "C6") (pin "2") (pinfunction "2_2") (pintype "passive"))
      (node (ref "C7") (pin "2") (pinfunction "2_2") (pintype "passive"))
      (node (ref "C8") (pin "2") (pinfunction "2_2") (pintype "passive"))
      (node (ref "C9") (pin "2") (pinfunction "2_2") (pintype "passive"))
      (node (ref "D3") (pin "2") (pinfunction "GND_2") (pintype "bidirectional"))
      (node (ref "D4") (pin "1") (pinfunction "K_1") (pintype "bidirectional"))
      (node (ref "EPD_C1") (pin "1") (pinfunction "1_1") (pintype "passive"))
      (node (ref "EPD_C10") (pin "1") (pinfunction "1_1") (pintype "passive"))
      (node (ref "EPD_C11") (pin "1") (pinfunction "1_1") (pintype "passive"))
      (node (ref "EPD_C12") (pin "1") (pinfunction "1_1") (pintype "passive"))
      (node (ref "EPD_C2") (pin "1") (pinfunction "1_1") (pintype "passive"))
      (node (ref "EPD_C5") (pin "1") (pinfunction "1_1") (pintype "passive"))
      (node (ref "EPD_C6") (pin "1") (pinfunction "1_1") (pintype "passive"))
      (node (ref "EPD_C7") (pin "1") (pinfunction "1_1") (pintype "passive"))
      (node (ref "EPD_C8") (pin "1") (pinfunction "1_1") (pintype "passive"))
      (node (ref "EPD_C9") (pin "1") (pinfunction "1_1") (pintype "passive"))
      (node (ref "IC1") (pin "D2") (pinfunction "GND_D2") (pintype "bidirectional"))
      (node (ref "IC2") (pin "B1") (pinfunction "IN/TRIG_B1") (pintype "bidirectional"))
      (node (ref "IC2") (pin "B3") (pinfunction "GND_B3") (pintype "bidirectional"))
      (node (ref "IC3") (pin "8") (pinfunction "GNDIO_8") (pintype "bidirectional"))
      (node (ref "IC3") (pin "9") (pinfunction "GND_9") (pintype "bidirectional"))
      (node (ref "IC9") (pin "B1") (pinfunction "VSEL_B1") (pintype "bidirectional"))
      (node (ref "IC9") (pin "C1") (pinfunction "AGND_C1") (pintype "bidirectional"))
      (node (ref "IC9") (pin "C2") (pinfunction "PGND_1_C2") (pintype "bidirectional"))
      (node (ref "IC9") (pin "C3") (pinfunction "PGND_2_C3") (pintype "bidirectional"))
      (node (ref "J1") (pin "17") (pinfunction "17_17") (pintype "bidirectional"))
      (node (ref "J1") (pin "8") (pinfunction "8_8") (pintype "bidirectional"))
      (node (ref "J1") (pin "MP1") (pinfunction "MP1_MP1") (pintype "bidirectional"))
      (node (ref "J1") (pin "MP2") (pinfunction "MP2_MP2") (pintype "bidirectional"))
      (node (ref "J2") (pin "3") (pinfunction "3_3") (pintype "bidirectional"))
      (node (ref "J2") (pin "5") (pinfunction "5_5") (pintype "bidirectional"))
      (node (ref "J4") (pin "A12_B1") (pinfunction "GND_A12_B1") (pintype "power_in"))
      (node (ref "J4") (pin "A1_B12") (pinfunction "GND_A1_B12") (pintype "power_in"))
      (node (ref "J4") (pin "SH1") (pinfunction "SHIELD_SH1") (pintype "passive"))
      (node (ref "J4") (pin "SH2") (pinfunction "SHIELD_SH2") (pintype "passive"))
      (node (ref "J4") (pin "SH3") (pinfunction "SHIELD_SH3") (pintype "passive"))
      (node (ref "J4") (pin "SH4") (pinfunction "SHIELD_SH4") (pintype "passive"))
      (node (ref "R1_USB") (pin "1") (pinfunction "1_1") (pintype "bidirectional"))
      (node (ref "R2_EP_DR") (pin "1") (pinfunction "1_1") (pintype "bidirectional"))
      (node (ref "R2_USB") (pin "2") (pinfunction "2_2") (pintype "bidirectional"))
      (node (ref "R3") (pin "1") (pinfunction "1_1") (pintype "bidirectional"))
      (node (ref "R9") (pin "1") (pinfunction "1_1") (pintype "bidirectional"))
      (node (ref "R_TYPE_SEL") (pin "1") (pinfunction "1_1") (pintype "bidirectional"))
      (node (ref "SJ1") (pin "1") (pinfunction "1_1") (pintype "passive"))
      (node (ref "SW_DN") (pin "1") (pinfunction "1_1") (pintype "passive"))
      (node (ref "SW_ENT") (pin "1") (pinfunction "1_1") (pintype "passive"))
      (node (ref "SW_UP") (pin "1") (pinfunction "1_1") (pintype "passive"))
      (node (ref "TP_BAT_GND") (pin "TP") (pinfunction "TP_TP") (pintype "input"))
      (node (ref "TP_GND") (pin "TP") (pinfunction "TP_TP") (pintype "input"))
      (node (ref "U1") (pin "P$74") (pinfunction "VSS_PAD_P$74") (pintype "bidirectional"))
      (node (ref "U1") (pin "P$75") (pinfunction "VSS_PAD_P$75") (pintype "bidirectional"))
      (node (ref "U1") (pin "P$76") (pinfunction "VSS_PAD_P$76") (pintype "bidirectional"))
      (node (ref "U1") (pin "P$77") (pinfunction "VSS_PAD_P$77") (pintype "bidirectional"))
      (node (ref "U1") (pin "P$78") (pinfunction "VSS_PAD_P$78") (pintype "bidirectional"))
      (node (ref "U1") (pin "P$79") (pinfunction "VSS_PAD_P$79") (pintype "bidirectional"))
      (node (ref "U1") (pin "P$80") (pinfunction "VSS_PAD_P$80") (pintype "bidirectional"))
      (node (ref "U1") (pin "P$81") (pinfunction "VSS_PAD_P$81") (pintype "bidirectional"))
      (node (ref "U1") (pin "P$82") (pinfunction "VSS_PAD_P$82") (pintype "bidirectional"))
      (node (ref "U1") (pin "P$83") (pinfunction "VSS_PAD_P$83") (pintype "bidirectional"))
      (node (ref "U1") (pin "P$84") (pinfunction "VSS_PAD_P$84") (pintype "bidirectional"))
      (node (ref "U1") (pin "P$85") (pinfunction "VSS_PAD_P$85") (pintype "bidirectional"))
      (node (ref "U1") (pin "P$86") (pinfunction "VSS_PAD_P$86") (pintype "bidirectional"))
      (node (ref "U1") (pin "P$87") (pinfunction "VSS_PAD_P$87") (pintype "bidirectional"))
      (node (ref "U1") (pin "P$88") (pinfunction "VSS_PAD_P$88") (pintype "bidirectional"))
      (node (ref "U1") (pin "P$89") (pinfunction "VSS_PAD_P$89") (pintype "bidirectional"))
      (node (ref "U1") (pin "P$90") (pinfunction "VSS_PAD_P$90") (pintype "bidirectional"))
      (node (ref "U1") (pin "P$B7") (pinfunction "VSS_P$B7") (pintype "power_in"))
      (node (ref "U1") (pin "P$F23") (pinfunction "VSS_PA_P$F23") (pintype "bidirectional"))
      (node (ref "U3") (pin "1") (pinfunction "CTG_1") (pintype "power_in"))
      (node (ref "U3") (pin "4") (pinfunction "GND_4") (pintype "power_in"))
      (node (ref "U3") (pin "6") (pinfunction "QSTRT_6") (pintype "input"))
      (node (ref "U3") (pin "9") (pinfunction "EP_9") (pintype "power_in"))
      (node (ref "X1") (pin "2") (pinfunction "2_2") (pintype "passive"))
      (node (ref "X1") (pin "4") (pinfunction "4_4") (pintype "passive"))
    )
    (net (code "25") (name "HAPTIC_EN{slash}1.4C") (class "Default")
      (node (ref "IC2") (pin "A1") (pinfunction "EN_A1") (pintype "bidirectional"))
    )
    (net (code "26") (name "HAPTIC_EN{slash}2.6A") (class "Default")
      (node (ref "U1") (pin "P$U1") (pinfunction "P0.12_P$U1") (pintype "bidirectional"))
    )
    (net (code "27") (name "IMU_INT1") (class "Default")
      (node (ref "IC3") (pin "5") (pinfunction "INT1_5") (pintype "bidirectional"))
      (node (ref "U1") (pin "P$N1") (pinfunction "P0.08_P$N1") (pintype "bidirectional"))
    )
    (net (code "28") (name "IMU_INT2") (class "Default")
      (node (ref "IC3") (pin "6") (pinfunction "INT2_6") (pintype "bidirectional"))
      (node (ref "U1") (pin "P$P2") (pinfunction "P1.08_P$P2") (pintype "bidirectional"))
    )
    (net (code "29") (name "LX1") (class "Default")
      (node (ref "IC9") (pin "B2") (pinfunction "SW1_1_B2") (pintype "bidirectional"))
      (node (ref "IC9") (pin "B3") (pinfunction "SW1_2_B3") (pintype "bidirectional"))
      (node (ref "L7") (pin "1") (pinfunction "1_1") (pintype "bidirectional"))
    )
    (net (code "30") (name "LX2") (class "Default")
      (node (ref "IC9") (pin "D2") (pinfunction "SW2_1_D2") (pintype "bidirectional"))
      (node (ref "IC9") (pin "D3") (pinfunction "SW2_2_D3") (pintype "bidirectional"))
      (node (ref "L7") (pin "2") (pinfunction "2_2") (pintype "bidirectional"))
    )
    (net (code "31") (name "MOSI{slash}1.5B") (class "Default")
      (node (ref "J1") (pin "14") (pinfunction "14_14") (pintype "bidirectional"))
    )
    (net (code "32") (name "MOSI{slash}2.2D") (class "Default")
      (node (ref "U1") (pin "P$B13") (pinfunction "P0.03/AIN1_P$B13") (pintype "bidirectional"))
    )
    (net (code "33") (name "N$6") (class "Default")
      (node (ref "C25") (pin "1") (pinfunction "1_1") (pintype "passive"))
      (node (ref "C33") (pin "1") (pinfunction "1_1") (pintype "passive"))
      (node (ref "IC9") (pin "E2") (pinfunction "VOUT_1_E2") (pintype "bidirectional"))
      (node (ref "IC9") (pin "E3") (pinfunction "VOUT_2_E3") (pintype "bidirectional"))
    )
    (net (code "34") (name "Net-(ANT1-FEED)") (class "Default")
      (node (ref "ANT1") (pin "1") (pinfunction "FEED_1") (pintype "input"))
      (node (ref "C22") (pin "1") (pinfunction "1_1") (pintype "passive"))
      (node (ref "C4") (pin "1") (pinfunction "1_1") (pintype "passive"))
      (node (ref "L1") (pin "2") (pinfunction "2_2") (pintype "passive"))
    )
    (net (code "35") (name "Net-(D2-K)") (class "Default")
      (node (ref "C2-EP-DR") (pin "1") (pinfunction "1_1") (pintype "passive"))
      (node (ref "D2") (pin "1") (pinfunction "K_1") (pintype "bidirectional"))
      (node (ref "D4") (pin "2") (pinfunction "A_2") (pintype "bidirectional"))
    )
    (net (code "36") (name "Net-(D5-A)") (class "Default")
      (node (ref "C2-EP-DR") (pin "2") (pinfunction "2_2") (pintype "passive"))
      (node (ref "D5") (pin "2") (pinfunction "A_2") (pintype "bidirectional"))
      (node (ref "L5") (pin "2") (pinfunction "2_2") (pintype "passive"))
      (node (ref "Q3") (pin "3") (pinfunction "D_3") (pintype "bidirectional"))
    )
    (net (code "37") (name "Net-(EPD_C1-Pad2)") (class "Default")
      (node (ref "EPD_C1") (pin "2") (pinfunction "2_2") (pintype "passive"))
      (node (ref "J1") (pin "5") (pinfunction "5_5") (pintype "bidirectional"))
    )
    (net (code "38") (name "Net-(EPD_C2-Pad2)") (class "Default")
      (node (ref "EPD_C2") (pin "2") (pinfunction "2_2") (pintype "passive"))
      (node (ref "J1") (pin "4") (pinfunction "4_4") (pintype "bidirectional"))
    )
    (net (code "39") (name "Net-(EPD_C6-Pad2)") (class "Default")
      (node (ref "EPD_C6") (pin "2") (pinfunction "2_2") (pintype "passive"))
      (node (ref "J1") (pin "18") (pinfunction "18_18") (pintype "bidirectional"))
    )
    (net (code "40") (name "Net-(EPD_C7-Pad2)") (class "Default")
      (node (ref "EPD_C7") (pin "2") (pinfunction "2_2") (pintype "passive"))
      (node (ref "J1") (pin "19") (pinfunction "19_19") (pintype "bidirectional"))
    )
    (net (code "41") (name "Net-(EPD_C8-Pad2)") (class "Default")
      (node (ref "EPD_C8") (pin "2") (pinfunction "2_2") (pintype "passive"))
      (node (ref "J1") (pin "20") (pinfunction "20_20") (pintype "bidirectional"))
    )
    (net (code "42") (name "Net-(EPD_C10-Pad2)") (class "Default")
      (node (ref "EPD_C10") (pin "2") (pinfunction "2_2") (pintype "passive"))
      (node (ref "J1") (pin "22") (pinfunction "22_22") (pintype "bidirectional"))
    )
    (net (code "43") (name "Net-(EPD_C12-Pad2)") (class "Default")
      (node (ref "EPD_C12") (pin "2") (pinfunction "2_2") (pintype "passive"))
      (node (ref "J1") (pin "24") (pinfunction "24_24") (pintype "bidirectional"))
    )
    (net (code "44") (name "Net-(IC1-TS{slash}MR)") (class "Default")
      (node (ref "IC1") (pin "D1") (pinfunction "TS/MR_D1") (pintype "bidirectional"))
      (node (ref "R9") (pin "2") (pinfunction "2_2") (pintype "bidirectional"))
    )
    (net (code "45") (name "Net-(IC2-REG)") (class "Default")
      (node (ref "C32") (pin "2") (pinfunction "2_2") (pintype "passive"))
      (node (ref "IC2") (pin "A2") (pinfunction "REG_A2") (pintype "bidirectional"))
    )
    (net (code "46") (name "Net-(IC3-SDO)") (class "Default")
      (node (ref "IC3") (pin "1") (pinfunction "SDO_1") (pintype "bidirectional"))
      (node (ref "R3") (pin "2") (pinfunction "2_2") (pintype "bidirectional"))
    )
    (net (code "47") (name "Net-(IC9-SCL)") (class "Default")
      (node (ref "IC9") (pin "D1") (pinfunction "SCL_D1") (pintype "bidirectional"))
      (node (ref "R4") (pin "2") (pinfunction "2_2") (pintype "bidirectional"))
    )
    (net (code "48") (name "Net-(IC9-SDA)") (class "Default")
      (node (ref "IC9") (pin "E1") (pinfunction "SDA_E1") (pintype "bidirectional"))
      (node (ref "R2") (pin "2") (pinfunction "2_2") (pintype "bidirectional"))
    )
    (net (code "49") (name "Net-(J4-CC1)") (class "Default")
      (node (ref "J4") (pin "A5") (pinfunction "CC1_A5") (pintype "bidirectional"))
      (node (ref "R1_USB") (pin "2") (pinfunction "2_2") (pintype "bidirectional"))
    )
    (net (code "50") (name "Net-(J4-CC2)") (class "Default")
      (node (ref "J4") (pin "B5") (pinfunction "CC2_B5") (pintype "bidirectional"))
      (node (ref "R2_USB") (pin "1") (pinfunction "1_1") (pintype "bidirectional"))
    )
    (net (code "51") (name "Net-(L2-Pad2)") (class "Default")
      (node (ref "L2") (pin "2") (pinfunction "2_2") (pintype "passive"))
      (node (ref "L3") (pin "1") (pinfunction "1_1") (pintype "passive"))
    )
    (net (code "52") (name "Net-(R1_EP_DR-Pad1)") (class "Default")
      (node (ref "R1_EP_DR") (pin "1") (pinfunction "1_1") (pintype "bidirectional"))
      (node (ref "R_TYPE_SEL") (pin "2") (pinfunction "2_2") (pintype "bidirectional"))
      (node (ref "SJ1") (pin "2") (pinfunction "2_2") (pintype "passive"))
    )
    (net (code "53") (name "Net-(U1-ANT)") (class "Default")
      (node (ref "C3") (pin "1") (pinfunction "1_1") (pintype "passive"))
      (node (ref "L1") (pin "1") (pinfunction "1_1") (pintype "passive"))
      (node (ref "U1") (pin "P$H23") (pinfunction "ANT_P$H23") (pintype "bidirectional"))
    )
    (net (code "54") (name "Net-(U1-DCC)") (class "Default")
      (node (ref "L2") (pin "1") (pinfunction "1_1") (pintype "passive"))
      (node (ref "U1") (pin "P$B3") (pinfunction "DCC_P$B3") (pintype "output"))
    )
    (net (code "55") (name "Net-(U1-DEC2)") (class "Default")
      (node (ref "C13") (pin "1") (pinfunction "1_1") (pintype "passive"))
      (node (ref "U1") (pin "P$A18") (pinfunction "DEC2_P$A18") (pintype "bidirectional"))
    )
    (net (code "56") (name "Net-(U1-DEC3V3)") (class "Default")
      (node (ref "C20") (pin "1") (pinfunction "1_1") (pintype "passive"))
      (node (ref "U1") (pin "P$AC5") (pinfunction "DEC3V3_P$AC5") (pintype "bidirectional"))
    )
    (net (code "57") (name "Net-(U1-DEC5)") (class "Default")
      (node (ref "C9") (pin "1") (pinfunction "1_1") (pintype "passive"))
      (node (ref "U1") (pin "P$N24") (pinfunction "DEC5_P$N24") (pintype "bidirectional"))
    )
    (net (code "58") (name "Net-(U1-XC1)") (class "Default")
      (node (ref "C1") (pin "1") (pinfunction "1_1") (pintype "passive"))
      (node (ref "U1") (pin "P$B24") (pinfunction "XC1_P$B24") (pintype "input"))
      (node (ref "X1") (pin "1") (pinfunction "1_1") (pintype "passive"))
    )
    (net (code "59") (name "Net-(U1-XC2)") (class "Default")
      (node (ref "C2") (pin "1") (pinfunction "1_1") (pintype "passive"))
      (node (ref "U1") (pin "P$A23") (pinfunction "XC2_P$A23") (pintype "output"))
      (node (ref "X1") (pin "3") (pinfunction "3_3") (pintype "passive"))
    )
    (net (code "60") (name "OUT+") (class "Default")
      (node (ref "IC2") (pin "A3") (pinfunction "OUT+_A3") (pintype "bidirectional"))
      (node (ref "TP_OP") (pin "TP") (pinfunction "TP_TP") (pintype "input"))
    )
    (net (code "61") (name "OUT-") (class "Default")
      (node (ref "IC2") (pin "C3") (pinfunction "OUT-_C3") (pintype "bidirectional"))
      (node (ref "TP_ON") (pin "TP") (pinfunction "TP_TP") (pintype "input"))
    )
    (net (code "62") (name "P0.00{slash}XL1") (class "Default")
      (node (ref "C17") (pin "2") (pinfunction "2_2") (pintype "passive"))
      (node (ref "U1") (pin "P$D2") (pinfunction "P0.00/XL1_P$D2") (pintype "bidirectional"))
      (node (ref "X2") (pin "1") (pinfunction "1_1") (pintype "passive"))
    )
    (net (code "63") (name "P0.01{slash}XL2") (class "Default")
      (node (ref "C18") (pin "2") (pinfunction "2_2") (pintype "passive"))
      (node (ref "U1") (pin "P$F2") (pinfunction "P0.01/XL2_P$F2") (pintype "bidirectional"))
      (node (ref "X2") (pin "2") (pinfunction "2_2") (pintype "passive"))
    )
    (net (code "64") (name "P0.04") (class "Default")
      (node (ref "U1") (pin "P$J1") (pinfunction "P0.04/AIN2_P$J1") (pintype "bidirectional"))
    )
    (net (code "65") (name "P0.09") (class "Default")
      (node (ref "U1") (pin "P$L24") (pinfunction "P0.09/NFC1_P$L24") (pintype "bidirectional"))
    )
    (net (code "66") (name "P0.13{slash}1.5D") (class "Default")
      (node (ref "C30") (pin "2") (pinfunction "2_2") (pintype "passive"))
      (node (ref "R5") (pin "1") (pinfunction "1_1") (pintype "bidirectional"))
      (node (ref "SW_UP") (pin "2") (pinfunction "2_2") (pintype "passive"))
    )
    (net (code "67") (name "P0.13{slash}2.6C") (class "Default")
      (node (ref "U1") (pin "P$AD8") (pinfunction "P0.13_P$AD8") (pintype "bidirectional"))
    )
    (net (code "68") (name "P0.14{slash}1.5D") (class "Default")
      (node (ref "C31") (pin "2") (pinfunction "2_2") (pintype "passive"))
      (node (ref "R8") (pin "1") (pinfunction "1_1") (pintype "bidirectional"))
      (node (ref "SW_ENT") (pin "2") (pinfunction "2_2") (pintype "passive"))
    )
    (net (code "69") (name "P0.14{slash}2.7C") (class "Default")
      (node (ref "U1") (pin "P$AC9") (pinfunction "P0.14_P$AC9") (pintype "bidirectional"))
    )
    (net (code "70") (name "P0.19") (class "Default")
      (node (ref "U1") (pin "P$AC15") (pinfunction "P0.19_P$AC15") (pintype "bidirectional"))
    )
    (net (code "71") (name "P0.20") (class "Default")
      (node (ref "U1") (pin "P$AD16") (pinfunction "P0.20_P$AD16") (pintype "bidirectional"))
    )
    (net (code "72") (name "P0.21") (class "Default")
      (node (ref "U1") (pin "P$AC17") (pinfunction "P0.21_P$AC17") (pintype "bidirectional"))
    )
    (net (code "73") (name "P0.22") (class "Default")
      (node (ref "U1") (pin "P$AD18") (pinfunction "P0.22_P$AD18") (pintype "bidirectional"))
    )
    (net (code "74") (name "P0.23") (class "Default")
      (node (ref "U1") (pin "P$AC19") (pinfunction "P0.23_P$AC19") (pintype "bidirectional"))
    )
    (net (code "75") (name "P0.24") (class "Default")
      (node (ref "U1") (pin "P$AD20") (pinfunction "P0.24_P$AD20") (pintype "bidirectional"))
    )
    (net (code "76") (name "P0.25") (class "Default")
      (node (ref "U1") (pin "P$AC21") (pinfunction "P0.25_P$AC21") (pintype "bidirectional"))
    )
    (net (code "77") (name "P0.26") (class "Default")
      (node (ref "U1") (pin "P$G1") (pinfunction "P0.26_P$G1") (pintype "bidirectional"))
    )
    (net (code "78") (name "P0.27") (class "Default")
      (node (ref "U1") (pin "P$H2") (pinfunction "P0.27_P$H2") (pintype "bidirectional"))
    )
    (net (code "79") (name "P0.28") (class "Default")
      (node (ref "U1") (pin "P$B11") (pinfunction "P0.28/AIN4_P$B11") (pintype "bidirectional"))
    )
    (net (code "80") (name "P0.29") (class "Default")
      (node (ref "U1") (pin "P$A10") (pinfunction "P0.29/AIN5_P$A10") (pintype "bidirectional"))
    )
    (net (code "81") (name "P0.30") (class "Default")
      (node (ref "U1") (pin "P$B9") (pinfunction "P0.30/AIN6_P$B9") (pintype "bidirectional"))
    )
    (net (code "82") (name "P0.31") (class "Default")
      (node (ref "U1") (pin "P$A8") (pinfunction "P0.31/AIN7_P$A8") (pintype "bidirectional"))
    )
    (net (code "83") (name "P1.01{slash}1.6C") (class "Default")
      (node (ref "DMG2305UX-7") (pin "1") (pinfunction "G_1") (pintype "bidirectional"))
      (node (ref "R_PWR_EPD") (pin "1") (pinfunction "1_1") (pintype "bidirectional"))
    )
    (net (code "84") (name "P1.01{slash}2.4B") (class "Default")
      (node (ref "U1") (pin "P$Y23") (pinfunction "P1.01_P$Y23") (pintype "bidirectional"))
    )
    (net (code "85") (name "P1.02{slash}1.6C") (class "Default")
      (node (ref "C29") (pin "2") (pinfunction "2_2") (pintype "passive"))
      (node (ref "R7") (pin "1") (pinfunction "1_1") (pintype "bidirectional"))
      (node (ref "SW_DN") (pin "2") (pinfunction "2_2") (pintype "passive"))
    )
    (net (code "86") (name "P1.02{slash}2.8C") (class "Default")
      (node (ref "U1") (pin "P$W24") (pinfunction "P1.02_P$W24") (pintype "bidirectional"))
    )
    (net (code "87") (name "P1.03") (class "Default")
      (node (ref "U1") (pin "P$V23") (pinfunction "P1.03_P$V23") (pintype "bidirectional"))
    )
    (net (code "88") (name "P1.04") (class "Default")
      (node (ref "U1") (pin "P$U24") (pinfunction "P1.04_P$U24") (pintype "bidirectional"))
    )
    (net (code "89") (name "P1.05") (class "Default")
      (node (ref "U1") (pin "P$T23") (pinfunction "P1.05_P$T23") (pintype "bidirectional"))
    )
    (net (code "90") (name "P1.06") (class "Default")
      (node (ref "U1") (pin "P$R24") (pinfunction "P1.06_P$R24") (pintype "bidirectional"))
    )
    (net (code "91") (name "P1.07") (class "Default")
      (node (ref "U1") (pin "P$P23") (pinfunction "P1.07_P$P23") (pintype "bidirectional"))
    )
    (net (code "92") (name "P1.09") (class "Default")
      (node (ref "U1") (pin "P$R1") (pinfunction "P1.09_P$R1") (pintype "bidirectional"))
    )
    (net (code "93") (name "P1.10") (class "Default")
      (node (ref "U1") (pin "P$A20") (pinfunction "P1.10_P$A20") (pintype "bidirectional"))
    )
    (net (code "94") (name "P1.11") (class "Default")
      (node (ref "U1") (pin "P$B19") (pinfunction "P1.11_P$B19") (pintype "bidirectional"))
    )
    (net (code "95") (name "P1.12") (class "Default")
      (node (ref "U1") (pin "P$B17") (pinfunction "P1.12_P$B17") (pintype "bidirectional"))
    )
    (net (code "96") (name "P1.13") (class "Default")
      (node (ref "U1") (pin "P$A16") (pinfunction "P1.13_P$A16") (pintype "bidirectional"))
    )
    (net (code "97") (name "P1.14") (class "Default")
      (node (ref "U1") (pin "P$B15") (pinfunction "P1.14_P$B15") (pintype "bidirectional"))
    )
    (net (code "98") (name "P1.15") (class "Default")
      (node (ref "U1") (pin "P$A14") (pinfunction "P1.15_P$A14") (pintype "bidirectional"))
    )
    (net (code "99") (name "PMIC_INT") (class "Default")
      (node (ref "IC1") (pin "A1") (pinfunction "~{INT}_A1") (pintype "bidirectional"))
      (node (ref "U1") (pin "P$T2") (pinfunction "P0.11_P$T2") (pintype "bidirectional"))
    )
    (net (code "100") (name "PREVGH") (class "Default")
      (node (ref "D5") (pin "1") (pinfunction "K_1") (pintype "bidirectional"))
      (node (ref "EPD_C9") (pin "2") (pinfunction "2_2") (pintype "passive"))
      (node (ref "J1") (pin "21") (pinfunction "21_21") (pintype "bidirectional"))
    )
    (net (code "101") (name "PREVGL") (class "Default")
      (node (ref "D2") (pin "2") (pinfunction "A_2") (pintype "bidirectional"))
      (node (ref "EPD_C11") (pin "2") (pinfunction "2_2") (pintype "passive"))
      (node (ref "J1") (pin "23") (pinfunction "23_23") (pintype "bidirectional"))
    )
    (net (code "102") (name "RESE") (class "Default")
      (node (ref "J1") (pin "3") (pinfunction "3_3") (pintype "bidirectional"))
      (node (ref "Q3") (pin "2") (pinfunction "S_2") (pintype "bidirectional"))
      (node (ref "R1_EP_DR") (pin "2") (pinfunction "2_2") (pintype "bidirectional"))
    )
    (net (code "103") (name "RESET") (class "Default")
      (node (ref "J2") (pin "6") (pinfunction "6_6") (pintype "bidirectional"))
      (node (ref "TP_RESET") (pin "TP") (pinfunction "TP_TP") (pintype "input"))
      (node (ref "U1") (pin "P$AC13") (pinfunction "P0.18/RESET_P$AC13") (pintype "bidirectional"))
    )
    (net (code "104") (name "SCK{slash}1.5B") (class "Default")
      (node (ref "J1") (pin "13") (pinfunction "13_13") (pintype "bidirectional"))
    )
    (net (code "105") (name "SCK{slash}2.2D") (class "Default")
      (node (ref "U1") (pin "P$A12") (pinfunction "P0.02/AIN0_P$A12") (pintype "bidirectional"))
    )
    (net (code "106") (name "SCL{slash}1.4C") (class "Default")
      (node (ref "IC2") (pin "C1") (pinfunction "SCL_C1") (pintype "bidirectional"))
      (node (ref "U3") (pin "7") (pinfunction "SCL_7") (pintype "input"))
    )
    (net (code "107") (name "SCL{slash}2.4C") (class "Default")
      (node (ref "IC1") (pin "B1") (pinfunction "SCL_B1") (pintype "bidirectional"))
      (node (ref "IC3") (pin "12") (pinfunction "SCX_12") (pintype "bidirectional"))
      (node (ref "R17") (pin "2") (pinfunction "2_2") (pintype "bidirectional"))
      (node (ref "R4") (pin "1") (pinfunction "1_1") (pintype "bidirectional"))
      (node (ref "TP1") (pin "TP") (pinfunction "TP_TP") (pintype "input"))
      (node (ref "U1") (pin "P$M2") (pinfunction "P0.07_P$M2") (pintype "bidirectional"))
    )
    (net (code "108") (name "SDA{slash}1.4C") (class "Default")
      (node (ref "IC2") (pin "B2") (pinfunction "SDA_B2") (pintype "bidirectional"))
      (node (ref "U3") (pin "8") (pinfunction "SDA_8") (pintype "bidirectional"))
    )
    (net (code "109") (name "SDA{slash}2.4C") (class "Default")
      (node (ref "IC1") (pin "C1") (pinfunction "SDA_C1") (pintype "bidirectional"))
      (node (ref "IC3") (pin "2") (pinfunction "SDX_2") (pintype "bidirectional"))
      (node (ref "R18") (pin "2") (pinfunction "2_2") (pintype "bidirectional"))
      (node (ref "R2") (pin "1") (pinfunction "1_1") (pintype "bidirectional"))
      (node (ref "TP2") (pin "TP") (pinfunction "TP_TP") (pintype "input"))
      (node (ref "U1") (pin "P$L1") (pinfunction "P0.06_P$L1") (pintype "bidirectional"))
    )
    (net (code "110") (name "SWDCLK") (class "Default")
      (node (ref "J2") (pin "4") (pinfunction "4_4") (pintype "bidirectional"))
      (node (ref "TP_SWDCLK") (pin "TP") (pinfunction "TP_TP") (pintype "input"))
      (node (ref "U1") (pin "P$AA24") (pinfunction "SWDCLK_P$AA24") (pintype "input"))
    )
    (net (code "111") (name "SWDIO") (class "Default")
      (node (ref "J2") (pin "2") (pinfunction "2_2") (pintype "bidirectional"))
      (node (ref "TP_SWDIO") (pin "TP") (pinfunction "TP_TP") (pintype "input"))
      (node (ref "U1") (pin "P$AC24") (pinfunction "SWDIO_P$AC24") (pintype "bidirectional"))
    )
    (net (code "112") (name "SWO") (class "Default")
      (node (ref "TP_SWO") (pin "TP") (pinfunction "TP_TP") (pintype "input"))
      (node (ref "U1") (pin "P$AD22") (pinfunction "P1.00_P$AD22") (pintype "bidirectional"))
    )
    (net (code "113") (name "VBAT{slash}1.2A") (class "Default")
      (node (ref "C27") (pin "2") (pinfunction "2_2") (pintype "passive"))
      (node (ref "TP_VBAT") (pin "TP") (pinfunction "TP_TP") (pintype "input"))
      (node (ref "U3") (pin "2") (pinfunction "CELL_2") (pintype "power_in"))
      (node (ref "U3") (pin "3") (pinfunction "VDD_3") (pintype "power_in"))
    )
    (net (code "114") (name "VBAT{slash}2.5C") (class "Default")
      (node (ref "C37") (pin "1") (pinfunction "1_1") (pintype "passive"))
      (node (ref "IC1") (pin "C2") (pinfunction "BAT_C2") (pintype "bidirectional"))
    )
    (net (code "115") (name "VBUS{slash}1.5D") (class "Default")
      (node (ref "C42") (pin "1") (pinfunction "1_1") (pintype "passive"))
      (node (ref "C43") (pin "1") (pinfunction "1_1") (pintype "passive"))
      (node (ref "D3") (pin "5") (pinfunction "VBUS_5") (pintype "bidirectional"))
      (node (ref "J4") (pin "A4_B9") (pinfunction "VBUS_A4_B9") (pintype "power_in"))
      (node (ref "J4") (pin "A9_B4") (pinfunction "VBUS_A9_B4") (pintype "power_in"))
    )
    (net (code "116") (name "VBUS{slash}2.6D") (class "Default")
      (node (ref "C21") (pin "1") (pinfunction "1_1") (pintype "passive"))
      (node (ref "C38") (pin "1") (pinfunction "1_1") (pintype "passive"))
      (node (ref "IC1") (pin "A2") (pinfunction "IN_A2") (pintype "bidirectional"))
      (node (ref "U1") (pin "P$AD2") (pinfunction "VBUS_P$AD2") (pintype "power_in"))
    )
    (net (code "117") (name "VREG") (class "Default")
      (node (ref "C23") (pin "2") (pinfunction "2_2") (pintype "passive"))
      (node (ref "C24") (pin "2") (pinfunction "2_2") (pintype "passive"))
      (node (ref "C39") (pin "1") (pinfunction "1_1") (pintype "passive"))
      (node (ref "IC1") (pin "B2") (pinfunction "SYS_B2") (pintype "bidirectional"))
      (node (ref "IC9") (pin "A1") (pinfunction "EN_A1") (pintype "bidirectional"))
      (node (ref "IC9") (pin "A2") (pinfunction "VIN_1_A2") (pintype "bidirectional"))
      (node (ref "IC9") (pin "A3") (pinfunction "VIN_2_A3") (pintype "bidirectional"))
      (node (ref "TP_VREG") (pin "TP") (pinfunction "TP_TP") (pintype "input"))
    )
    (net (code "118") (name "unconnected-(ANT1-NC-Pad2)") (class "Default")
      (node (ref "ANT1") (pin "2") (pinfunction "NC_2") (pintype "no_connect"))
    )
    (net (code "119") (name "unconnected-(IC3-ASCL-Pad11)") (class "Default")
      (node (ref "IC3") (pin "11") (pinfunction "ASCL_11") (pintype "bidirectional"))
    )
    (net (code "120") (name "unconnected-(IC3-ASDA-Pad4)") (class "Default")
      (node (ref "IC3") (pin "4") (pinfunction "ASDA_4") (pintype "bidirectional"))
    )
    (net (code "121") (name "unconnected-(J1-Pad1)") (class "Default")
      (node (ref "J1") (pin "1") (pinfunction "1_1") (pintype "bidirectional"))
    )
    (net (code "122") (name "unconnected-(J1-Pad6)") (class "Default")
      (node (ref "J1") (pin "6") (pinfunction "6_6") (pintype "bidirectional"))
    )
    (net (code "123") (name "unconnected-(J1-Pad7)") (class "Default")
      (node (ref "J1") (pin "7") (pinfunction "7_7") (pintype "bidirectional"))
    )
    (net (code "124") (name "unconnected-(J4-SBU1-PadA8)") (class "Default")
      (node (ref "J4") (pin "A8") (pinfunction "SBU1_A8") (pintype "bidirectional"))
    )
    (net (code "125") (name "unconnected-(J4-SBU2-PadB8)") (class "Default")
      (node (ref "J4") (pin "B8") (pinfunction "SBU2_B8") (pintype "bidirectional"))
    )
    (net (code "126") (name "unconnected-(U1-DCCH-PadP$AB2)") (class "Default")
      (node (ref "U1") (pin "P$AB2") (pinfunction "DCCH_P$AB2") (pintype "bidirectional"))
    )
  )
)
